# Standalone.net
KiCad netlist of a schematic drawn in Altium Designer
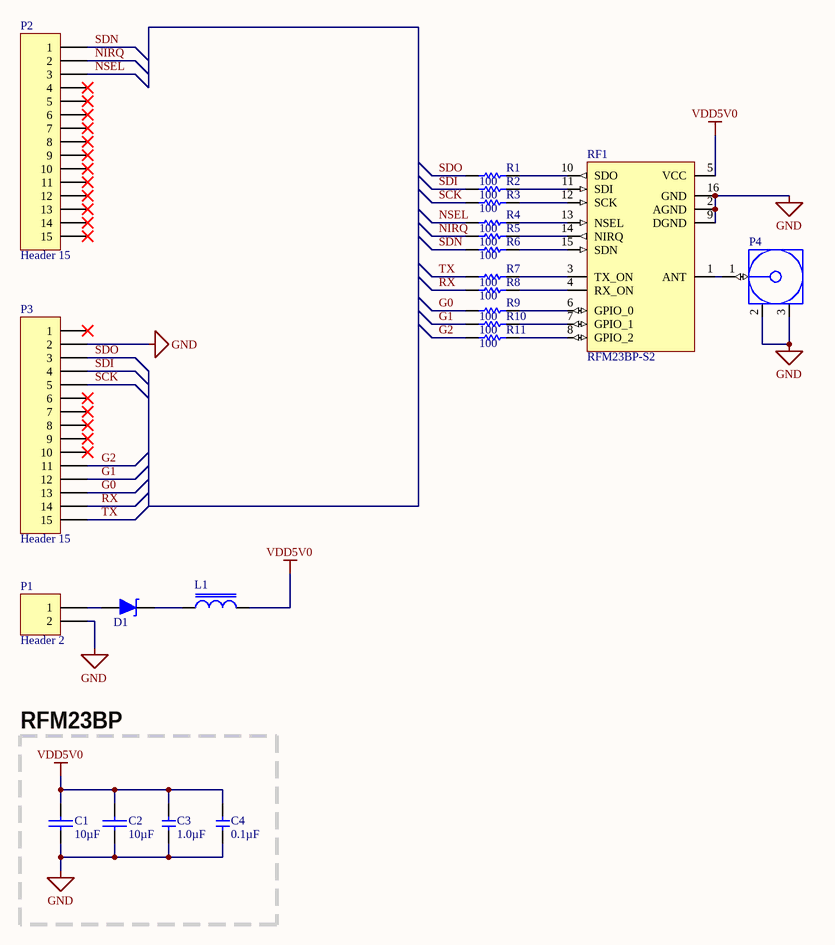
[diagram p0: Standalone.SchDoc]

(export (version "E")
  (design (tool "Eeschema 10.0.6"))
  (components
    (comp (ref "C1")
      (value "CAP CER 10UF 25V 10% X5R 1206")
      (footprint "Capacitors:1206_CAP")
      (fields
        (field (name "MANUFACTURER") "Murata Electronics North America")
        (field (name "MANUFACTURER PART NUMBER") "GRM31CR61E106KA12L")
        (field (name "TOLERANCE") "±10%")
        (field (name "CAPACITANCE") "10µF")
      )
      (libsource (lib "Capacitors") (part "GRM31CR61E106KA12L"))
    )
    (comp (ref "C2")
      (value "CAP CER 10UF 25V 10% X5R 1206")
      (footprint "Capacitors:1206_CAP")
      (fields
        (field (name "MANUFACTURER") "Murata Electronics North America")
        (field (name "MANUFACTURER PART NUMBER") "GRM31CR61E106KA12L")
        (field (name "TOLERANCE") "±10%")
        (field (name "CAPACITANCE") "10µF")
      )
      (libsource (lib "Capacitors") (part "GRM31CR61E106KA12L"))
    )
    (comp (ref "C3")
      (value "CAP CER 1UF 16V 10% X7R 0603")
      (footprint "Capacitors:0603_CAP")
      (fields
        (field (name "MANUFACTURER") "Kemet")
        (field (name "MANUFACTURER PART NUMBER") "C0603C105K4RACTU")
        (field (name "TOLERANCE") "±10%")
        (field (name "CAPACITANCE") "1.0µF")
      )
      (libsource (lib "Capacitors") (part "C0603C105K4RACTU"))
    )
    (comp (ref "C4")
      (value "CAP CER 0.1UF 16V 10% X7R 0603")
      (footprint "Capacitors:0603_CAP")
      (fields
        (field (name "MANUFACTURER") "Kemet")
        (field (name "MANUFACTURER PART NUMBER") "C0603C104K4RACTU")
        (field (name "TOLERANCE") "±10%")
        (field (name "CAPACITANCE") "0.1µF")
      )
      (libsource (lib "Capacitors") (part "C0603C104K4RACTU"))
    )
    (comp (ref "D1")
      (value "PMEG2020AEA,115")
      (footprint "Almtracker3_SHX1:SOD323 (SC76)")
      (description "SCHOTTKY RECT 20V 2A SOD323")
      (fields (field (name "MANUFACTURER") "NXP Semiconductors"))
      (libsource (lib "SHX1") (part "PMEG2020AEA,115"))
    )
    (comp (ref "L1")
      (value "FERRITE CHIP 180 OHM 2A 0603")
      (footprint "0603")
      (fields
        (field (name "MANUFACTURER") "TDK Corporation")
        (field (name "MANUFACTURER PART NUMBER") "MPZ1608S181A")
      )
      (libsource (lib "SHX1") (part "MPZ1608S181A"))
    )
    (comp (ref "P1")
      (value "Header 2")
      (footprint "HDR1X2")
      (description "Header, 2-Pin")
      (fields (field (name "PUBLISHER") "Altium Limited"))
      (libsource (lib "Miscellaneous Connectors") (part "Header 2"))
    )
    (comp (ref "P2")
      (value "Header 15")
      (footprint "HDR1X15")
      (description "CONN HEADER FEMALE 15POS.1\" TIN")
      (fields (field (name "PUBLISHER") "Altium Limited"))
      (libsource (lib "Miscellaneous Connectors") (part "Header 15"))
    )
    (comp (ref "P3")
      (value "Header 15")
      (footprint "HDR1X15")
      (description "CONN HEADER FEMALE 15POS.1\" TIN")
      (fields (field (name "PUBLISHER") "Altium Limited"))
      (libsource (lib "Miscellaneous Connectors") (part "Header 15"))
    )
    (comp (ref "P4")
      (value "MULTICOMP - 19-70-TGG - JACK SMA, END LAUNCH")
      (footprint "Almtracker3_SHX1:SMA Connector")
      (fields (field (name "MANUFACTURER") "MULTICOMP") (field (name "MANUFACTURER PART NUMBER") "19-70-TGG"))
      (libsource (lib "SHX1") (part "19-70-TGG"))
    )
    (comp (ref "R1")
      (value "Stackpole Electronics Inc")
      (footprint "Resistors:0402")
      (description "RES 100 OHM 1/16W 1% 0402 SMD")
      (fields
        (field (name "MANUFACTURER PART NUMBER") "RMCF0402FT100R")
        (field (name "TOLERANCE") "±1%")
        (field (name "RESISTANCE (OHMS)") "100")
      )
      (libsource (lib "Resistors") (part "RMCF0402FT100R"))
    )
    (comp (ref "R2")
      (value "Stackpole Electronics Inc")
      (footprint "Resistors:0402")
      (description "RES 100 OHM 1/16W 1% 0402 SMD")
      (fields
        (field (name "MANUFACTURER PART NUMBER") "RMCF0402FT100R")
        (field (name "TOLERANCE") "±1%")
        (field (name "RESISTANCE (OHMS)") "100")
      )
      (libsource (lib "Resistors") (part "RMCF0402FT100R"))
    )
    (comp (ref "R3")
      (value "Stackpole Electronics Inc")
      (footprint "Resistors:0402")
      (description "RES 100 OHM 1/16W 1% 0402 SMD")
      (fields
        (field (name "MANUFACTURER PART NUMBER") "RMCF0402FT100R")
        (field (name "TOLERANCE") "±1%")
        (field (name "RESISTANCE (OHMS)") "100")
      )
      (libsource (lib "Resistors") (part "RMCF0402FT100R"))
    )
    (comp (ref "R4")
      (value "Stackpole Electronics Inc")
      (footprint "Resistors:0402")
      (description "RES 100 OHM 1/16W 1% 0402 SMD")
      (fields
        (field (name "MANUFACTURER PART NUMBER") "RMCF0402FT100R")
        (field (name "TOLERANCE") "±1%")
        (field (name "RESISTANCE (OHMS)") "100")
      )
      (libsource (lib "Resistors") (part "RMCF0402FT100R"))
    )
    (comp (ref "R5")
      (value "Stackpole Electronics Inc")
      (footprint "Resistors:0402")
      (description "RES 100 OHM 1/16W 1% 0402 SMD")
      (fields
        (field (name "MANUFACTURER PART NUMBER") "RMCF0402FT100R")
        (field (name "TOLERANCE") "±1%")
        (field (name "RESISTANCE (OHMS)") "100")
      )
      (libsource (lib "Resistors") (part "RMCF0402FT100R"))
    )
    (comp (ref "R6")
      (value "Stackpole Electronics Inc")
      (footprint "Resistors:0402")
      (description "RES 100 OHM 1/16W 1% 0402 SMD")
      (fields
        (field (name "MANUFACTURER PART NUMBER") "RMCF0402FT100R")
        (field (name "TOLERANCE") "±1%")
        (field (name "RESISTANCE (OHMS)") "100")
      )
      (libsource (lib "Resistors") (part "RMCF0402FT100R"))
    )
    (comp (ref "R7")
      (value "Stackpole Electronics Inc")
      (footprint "Resistors:0402")
      (description "RES 100 OHM 1/16W 1% 0402 SMD")
      (fields
        (field (name "MANUFACTURER PART NUMBER") "RMCF0402FT100R")
        (field (name "TOLERANCE") "±1%")
        (field (name "RESISTANCE (OHMS)") "100")
      )
      (libsource (lib "Resistors") (part "RMCF0402FT100R"))
    )
    (comp (ref "R8")
      (value "Stackpole Electronics Inc")
      (footprint "Resistors:0402")
      (description "RES 100 OHM 1/16W 1% 0402 SMD")
      (fields
        (field (name "MANUFACTURER PART NUMBER") "RMCF0402FT100R")
        (field (name "TOLERANCE") "±1%")
        (field (name "RESISTANCE (OHMS)") "100")
      )
      (libsource (lib "Resistors") (part "RMCF0402FT100R"))
    )
    (comp (ref "R9")
      (value "Stackpole Electronics Inc")
      (footprint "Resistors:0402")
      (description "RES 100 OHM 1/16W 1% 0402 SMD")
      (fields
        (field (name "MANUFACTURER PART NUMBER") "RMCF0402FT100R")
        (field (name "TOLERANCE") "±1%")
        (field (name "RESISTANCE (OHMS)") "100")
      )
      (libsource (lib "Resistors") (part "RMCF0402FT100R"))
    )
    (comp (ref "R10")
      (value "Stackpole Electronics Inc")
      (footprint "Resistors:0402")
      (description "RES 100 OHM 1/16W 1% 0402 SMD")
      (fields
        (field (name "MANUFACTURER PART NUMBER") "RMCF0402FT100R")
        (field (name "TOLERANCE") "±1%")
        (field (name "RESISTANCE (OHMS)") "100")
      )
      (libsource (lib "Resistors") (part "RMCF0402FT100R"))
    )
    (comp (ref "R11")
      (value "Stackpole Electronics Inc")
      (footprint "Resistors:0402")
      (description "RES 100 OHM 1/16W 1% 0402 SMD")
      (fields
        (field (name "MANUFACTURER PART NUMBER") "RMCF0402FT100R")
        (field (name "TOLERANCE") "±1%")
        (field (name "RESISTANCE (OHMS)") "100")
      )
      (libsource (lib "Resistors") (part "RMCF0402FT100R"))
    )
    (comp (ref "RF1")
      (value "RFM23BP-S2")
      (footprint "RFM23BP-S2")
      (description "UHF 1W Transceiver")
      (libsource (lib "HoperRF") (part "RFM23BP-S2"))
    )
  )
  (nets
    (net (code "1") (name "/G0") (class "Default")
      (node (ref "P3") (pin "13") (pinfunction "13_13") (pintype "passive"))
      (node (ref "R9") (pin "1") (pinfunction "1_1") (pintype "passive"))
    )
    (net (code "2") (name "/G1") (class "Default")
      (node (ref "P3") (pin "12") (pinfunction "12_12") (pintype "passive"))
      (node (ref "R10") (pin "1") (pinfunction "1_1") (pintype "passive"))
    )
    (net (code "3") (name "/G2") (class "Default")
      (node (ref "P3") (pin "11") (pinfunction "11_11") (pintype "passive"))
      (node (ref "R11") (pin "1") (pinfunction "1_1") (pintype "passive"))
    )
    (net (code "4") (name "/NIRQ") (class "Default")
      (node (ref "P2") (pin "2") (pinfunction "2_2") (pintype "passive"))
      (node (ref "R5") (pin "1") (pinfunction "1_1") (pintype "passive"))
    )
    (net (code "5") (name "/NSEL") (class "Default")
      (node (ref "P2") (pin "3") (pinfunction "3_3") (pintype "passive"))
      (node (ref "R4") (pin "1") (pinfunction "1_1") (pintype "passive"))
    )
    (net (code "6") (name "/RX") (class "Default")
      (node (ref "P3") (pin "14") (pinfunction "14_14") (pintype "passive"))
      (node (ref "R8") (pin "1") (pinfunction "1_1") (pintype "passive"))
    )
    (net (code "7") (name "/SCK") (class "Default")
      (node (ref "P3") (pin "5") (pinfunction "5_5") (pintype "passive"))
      (node (ref "R3") (pin "1") (pinfunction "1_1") (pintype "passive"))
    )
    (net (code "8") (name "/SDI") (class "Default")
      (node (ref "P3") (pin "4") (pinfunction "4_4") (pintype "passive"))
      (node (ref "R2") (pin "1") (pinfunction "1_1") (pintype "passive"))
    )
    (net (code "9") (name "/SDN") (class "Default")
      (node (ref "P2") (pin "1") (pinfunction "1_1") (pintype "passive"))
      (node (ref "R6") (pin "1") (pinfunction "1_1") (pintype "passive"))
    )
    (net (code "10") (name "/SDO") (class "Default")
      (node (ref "P3") (pin "3") (pinfunction "3_3") (pintype "passive"))
      (node (ref "R1") (pin "1") (pinfunction "1_1") (pintype "passive"))
    )
    (net (code "11") (name "/TX") (class "Default")
      (node (ref "P3") (pin "15") (pinfunction "15_15") (pintype "passive"))
      (node (ref "R7") (pin "1") (pinfunction "1_1") (pintype "passive"))
    )
    (net (code "12") (name "GND") (class "Default")
      (node (ref "C1") (pin "2") (pintype "passive"))
      (node (ref "C2") (pin "2") (pintype "passive"))
      (node (ref "C3") (pin "2") (pintype "passive"))
      (node (ref "C4") (pin "2") (pintype "passive"))
      (node (ref "P1") (pin "2") (pinfunction "2_2") (pintype "passive"))
      (node (ref "P3") (pin "2") (pinfunction "2_2") (pintype "passive"))
      (node (ref "P4") (pin "2") (pinfunction "GND_2") (pintype "power_in"))
      (node (ref "P4") (pin "3") (pinfunction "GND_3") (pintype "power_in"))
      (node (ref "RF1") (pin "16") (pinfunction "GND_16") (pintype "power_in"))
      (node (ref "RF1") (pin "2") (pinfunction "AGND_2") (pintype "power_in"))
      (node (ref "RF1") (pin "9") (pinfunction "DGND_9") (pintype "power_in"))
    )
    (net (code "13") (name "Net-(D1-A)") (class "Default")
      (node (ref "D1") (pin "2") (pinfunction "A_2") (pintype "passive"))
      (node (ref "P1") (pin "1") (pinfunction "1_1") (pintype "passive"))
    )
    (net (code "14") (name "Net-(D1-C)") (class "Default")
      (node (ref "D1") (pin "1") (pinfunction "C_1") (pintype "passive"))
      (node (ref "L1") (pin "1") (pinfunction "1_1") (pintype "passive"))
    )
    (net (code "15") (name "Net-(P4-Signal)") (class "Default")
      (node (ref "P4") (pin "1") (pinfunction "Signal_1") (pintype "bidirectional"))
      (node (ref "RF1") (pin "1") (pinfunction "ANT_1") (pintype "passive"))
    )
    (net (code "16") (name "Net-(RF1-GPIO_0)") (class "Default")
      (node (ref "R9") (pin "2") (pinfunction "2_2") (pintype "passive"))
      (node (ref "RF1") (pin "6") (pinfunction "GPIO_0_6") (pintype "bidirectional"))
    )
    (net (code "17") (name "Net-(RF1-GPIO_1)") (class "Default")
      (node (ref "R10") (pin "2") (pinfunction "2_2") (pintype "passive"))
      (node (ref "RF1") (pin "7") (pinfunction "GPIO_1_7") (pintype "bidirectional"))
    )
    (net (code "18") (name "Net-(RF1-GPIO_2)") (class "Default")
      (node (ref "R11") (pin "2") (pinfunction "2_2") (pintype "passive"))
      (node (ref "RF1") (pin "8") (pinfunction "GPIO_2_8") (pintype "bidirectional"))
    )
    (net (code "19") (name "Net-(RF1-NIRQ)") (class "Default")
      (node (ref "R5") (pin "2") (pinfunction "2_2") (pintype "passive"))
      (node (ref "RF1") (pin "14") (pinfunction "NIRQ_14") (pintype "output"))
    )
    (net (code "20") (name "Net-(RF1-NSEL)") (class "Default")
      (node (ref "R4") (pin "2") (pinfunction "2_2") (pintype "passive"))
      (node (ref "RF1") (pin "13") (pinfunction "NSEL_13") (pintype "input"))
    )
    (net (code "21") (name "Net-(RF1-RX_ON)") (class "Default")
      (node (ref "R8") (pin "2") (pinfunction "2_2") (pintype "passive"))
      (node (ref "RF1") (pin "4") (pinfunction "RX_ON_4") (pintype "passive"))
    )
    (net (code "22") (name "Net-(RF1-SCK)") (class "Default")
      (node (ref "R3") (pin "2") (pinfunction "2_2") (pintype "passive"))
      (node (ref "RF1") (pin "12") (pinfunction "SCK_12") (pintype "input"))
    )
    (net (code "23") (name "Net-(RF1-SDI)") (class "Default")
      (node (ref "R2") (pin "2") (pinfunction "2_2") (pintype "passive"))
      (node (ref "RF1") (pin "11") (pinfunction "SDI_11") (pintype "input"))
    )
    (net (code "24") (name "Net-(RF1-SDN)") (class "Default")
      (node (ref "R6") (pin "2") (pinfunction "2_2") (pintype "passive"))
      (node (ref "RF1") (pin "15") (pinfunction "SDN_15") (pintype "input"))
    )
    (net (code "25") (name "Net-(RF1-SDO)") (class "Default")
      (node (ref "R1") (pin "2") (pinfunction "2_2") (pintype "passive"))
      (node (ref "RF1") (pin "10") (pinfunction "SDO_10") (pintype "output"))
    )
    (net (code "26") (name "Net-(RF1-TX_ON)") (class "Default")
      (node (ref "R7") (pin "2") (pinfunction "2_2") (pintype "passive"))
      (node (ref "RF1") (pin "3") (pinfunction "TX_ON_3") (pintype "passive"))
    )
    (net (code "27") (name "VDD5V0") (class "Default")
      (node (ref "C1") (pin "1") (pintype "passive"))
      (node (ref "C2") (pin "1") (pintype "passive"))
      (node (ref "C3") (pin "1") (pintype "passive"))
      (node (ref "C4") (pin "1") (pintype "passive"))
      (node (ref "L1") (pin "2") (pinfunction "2_2") (pintype "passive"))
      (node (ref "RF1") (pin "5") (pinfunction "VCC_5") (pintype "power_in"))
    )
    (net (code "28") (name "unconnected-(P2-Pad4)") (class "Default")
      (node (ref "P2") (pin "4") (pinfunction "4_4") (pintype "passive+no_connect"))
    )
    (net (code "29") (name "unconnected-(P2-Pad5)") (class "Default")
      (node (ref "P2") (pin "5") (pinfunction "5_5") (pintype "passive+no_connect"))
    )
    (net (code "30") (name "unconnected-(P2-Pad6)") (class "Default")
      (node (ref "P2") (pin "6") (pinfunction "6_6") (pintype "passive+no_connect"))
    )
    (net (code "31") (name "unconnected-(P2-Pad7)") (class "Default")
      (node (ref "P2") (pin "7") (pinfunction "7_7") (pintype "passive+no_connect"))
    )
    (net (code "32") (name "unconnected-(P2-Pad8)") (class "Default")
      (node (ref "P2") (pin "8") (pinfunction "8_8") (pintype "passive+no_connect"))
    )
    (net (code "33") (name "unconnected-(P2-Pad9)") (class "Default")
      (node (ref "P2") (pin "9") (pinfunction "9_9") (pintype "passive+no_connect"))
    )
    (net (code "34") (name "unconnected-(P2-Pad10)") (class "Default")
      (node (ref "P2") (pin "10") (pinfunction "10_10") (pintype "passive+no_connect"))
    )
    (net (code "35") (name "unconnected-(P2-Pad11)") (class "Default")
      (node (ref "P2") (pin "11") (pinfunction "11_11") (pintype "passive+no_connect"))
    )
    (net (code "36") (name "unconnected-(P2-Pad12)") (class "Default")
      (node (ref "P2") (pin "12") (pinfunction "12_12") (pintype "passive+no_connect"))
    )
    (net (code "37") (name "unconnected-(P2-Pad13)") (class "Default")
      (node (ref "P2") (pin "13") (pinfunction "13_13") (pintype "passive+no_connect"))
    )
    (net (code "38") (name "unconnected-(P2-Pad14)") (class "Default")
      (node (ref "P2") (pin "14") (pinfunction "14_14") (pintype "passive+no_connect"))
    )
    (net (code "39") (name "unconnected-(P2-Pad15)") (class "Default")
      (node (ref "P2") (pin "15") (pinfunction "15_15") (pintype "passive+no_connect"))
    )
    (net (code "40") (name "unconnected-(P3-Pad1)") (class "Default")
      (node (ref "P3") (pin "1") (pinfunction "1_1") (pintype "passive+no_connect"))
    )
    (net (code "41") (name "unconnected-(P3-Pad6)") (class "Default")
      (node (ref "P3") (pin "6") (pinfunction "6_6") (pintype "passive+no_connect"))
    )
    (net (code "42") (name "unconnected-(P3-Pad7)") (class "Default")
      (node (ref "P3") (pin "7") (pinfunction "7_7") (pintype "passive+no_connect"))
    )
    (net (code "43") (name "unconnected-(P3-Pad8)") (class "Default")
      (node (ref "P3") (pin "8") (pinfunction "8_8") (pintype "passive+no_connect"))
    )
    (net (code "44") (name "unconnected-(P3-Pad9)") (class "Default")
      (node (ref "P3") (pin "9") (pinfunction "9_9") (pintype "passive+no_connect"))
    )
    (net (code "45") (name "unconnected-(P3-Pad10)") (class "Default")
      (node (ref "P3") (pin "10") (pinfunction "10_10") (pintype "passive+no_connect"))
    )
    (net (code "46") (name "unconnected-(RF1-N.C-Pad1)") (class "Default")
      (node (ref "RF1") (pin "1") (pinfunction "N.C_1") (pintype "tri_state"))
    )
    (net (code "47") (name "unconnected-(RF1-N.C-Pad4)") (class "Default")
      (node (ref "RF1") (pin "4") (pinfunction "N.C_4") (pintype "tri_state"))
    )
    (net (code "48") (name "unconnected-(RF1-N.C-Pad8)") (class "Default")
      (node (ref "RF1") (pin "8") (pinfunction "N.C_8") (pintype "tri_state"))
    )
    (net (code "49") (name "unconnected-(RF1-N.C-Pad9)") (class "Default")
      (node (ref "RF1") (pin "9") (pinfunction "N.C_9") (pintype "tri_state"))
    )
    (net (code "50") (name "unconnected-(RF1-N.C-Pad14)") (class "Default")
      (node (ref "RF1") (pin "14") (pinfunction "N.C_14") (pintype "tri_state"))
    )
  )
)
